# Archimedes_Endstop_Kati.net
KiCad netlist of a schematic drawn in Altium Designer
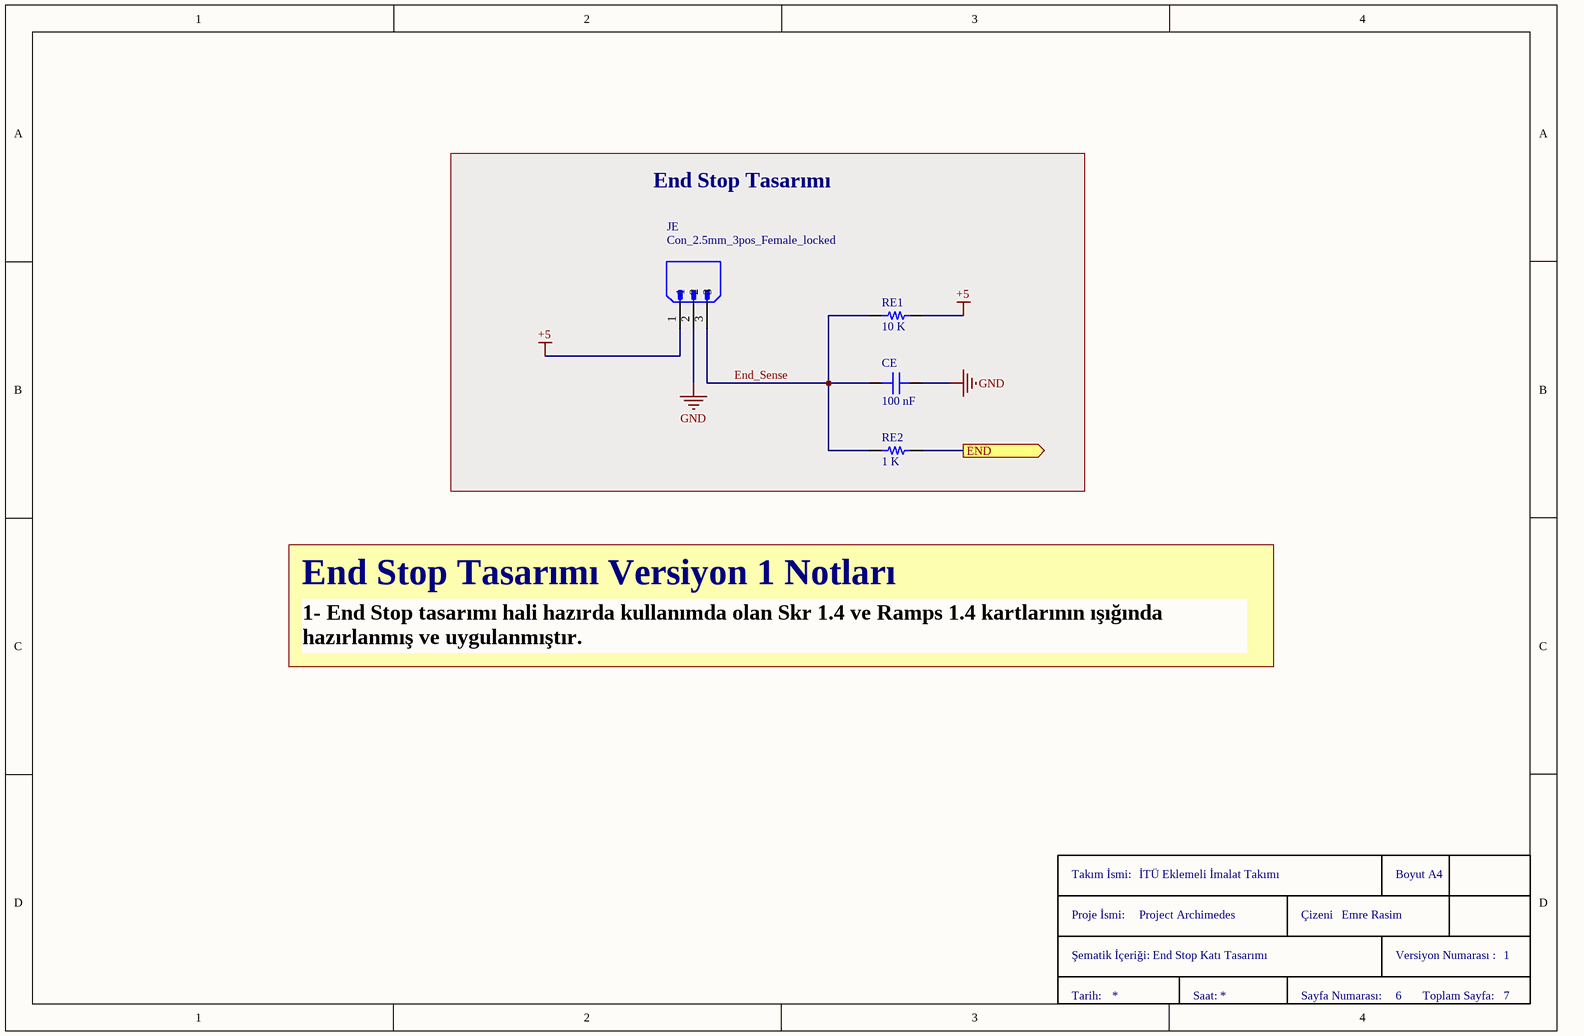
[diagram p0: Archimedes_Endstop_Kati.SchDoc]

(export (version "E")
  (design (tool "Eeschema 10.0.6"))
  (components
    (comp (ref "CE")
      (value "100 nF")
      (footprint "CAP 0805/2012")
      (description "100 nF  and 50 Volt Ceramic Capacitor 805 pack with X7R rating")
      (libsource (lib "Pasifler") (part "Capacitor 805"))
    )
    (comp (ref "JE")
      (value "Con_2.5mm_3pos_Female_locked")
      (footprint "Con_3lead_2.5mm_locked")
      (description "3 lead female locked connector for 3d printer limit switch")
      (fields (field (name "MP") "B3B-XH-A(LF)(SN)"))
      (libsource (lib "Buck") (part "Con_2.5mm_3pos_Female_locked"))
    )
    (comp (ref "RE1")
      (value "10 K")
      (footprint "RES 0805/2012")
      (description "10 K ohm Resistor  with 805 pack and %1 tolerance rating")
      (libsource (lib "Pasifler") (part "Resistor 805"))
    )
    (comp (ref "RE2")
      (value "1 K")
      (footprint "RES 0805/2012")
      (description "1 K ohm Resistor  with 805 pack and %1 tolerance rating")
      (libsource (lib "Pasifler") (part "Resistor 805"))
    )
    (comp (ref "TitleBlock-A4")
      (value "TitleBlock-A4")
      (description "Title Block for İTU eklemeli imalat takımı")
      (libsource (lib "EKIM_Team_Main") (part "TitleBlock-A4"))
    )
  )
  (nets
    (net (code "1") (name "+5") (class "Default")
      (node (ref "JE") (pin "1") (pinfunction "1_1") (pintype "passive"))
      (node (ref "RE1") (pin "2") (pinfunction "2_2") (pintype "passive"))
    )
    (net (code "2") (name "/END") (class "Default")
      (node (ref "RE2") (pin "2") (pinfunction "2_2") (pintype "passive"))
    )
    (net (code "3") (name "/End_Sense") (class "Default")
      (node (ref "CE") (pin "1") (pinfunction "1_1") (pintype "passive"))
      (node (ref "JE") (pin "3") (pinfunction "3_3") (pintype "passive"))
      (node (ref "RE1") (pin "1") (pinfunction "1_1") (pintype "passive"))
      (node (ref "RE2") (pin "1") (pinfunction "1_1") (pintype "passive"))
    )
    (net (code "4") (name "GND") (class "Default")
      (node (ref "CE") (pin "2") (pinfunction "2_2") (pintype "passive"))
      (node (ref "JE") (pin "2") (pinfunction "2_2") (pintype "passive"))
    )
  )
)
